# Modules.net
KiCad netlist of a schematic drawn in Altium Designer
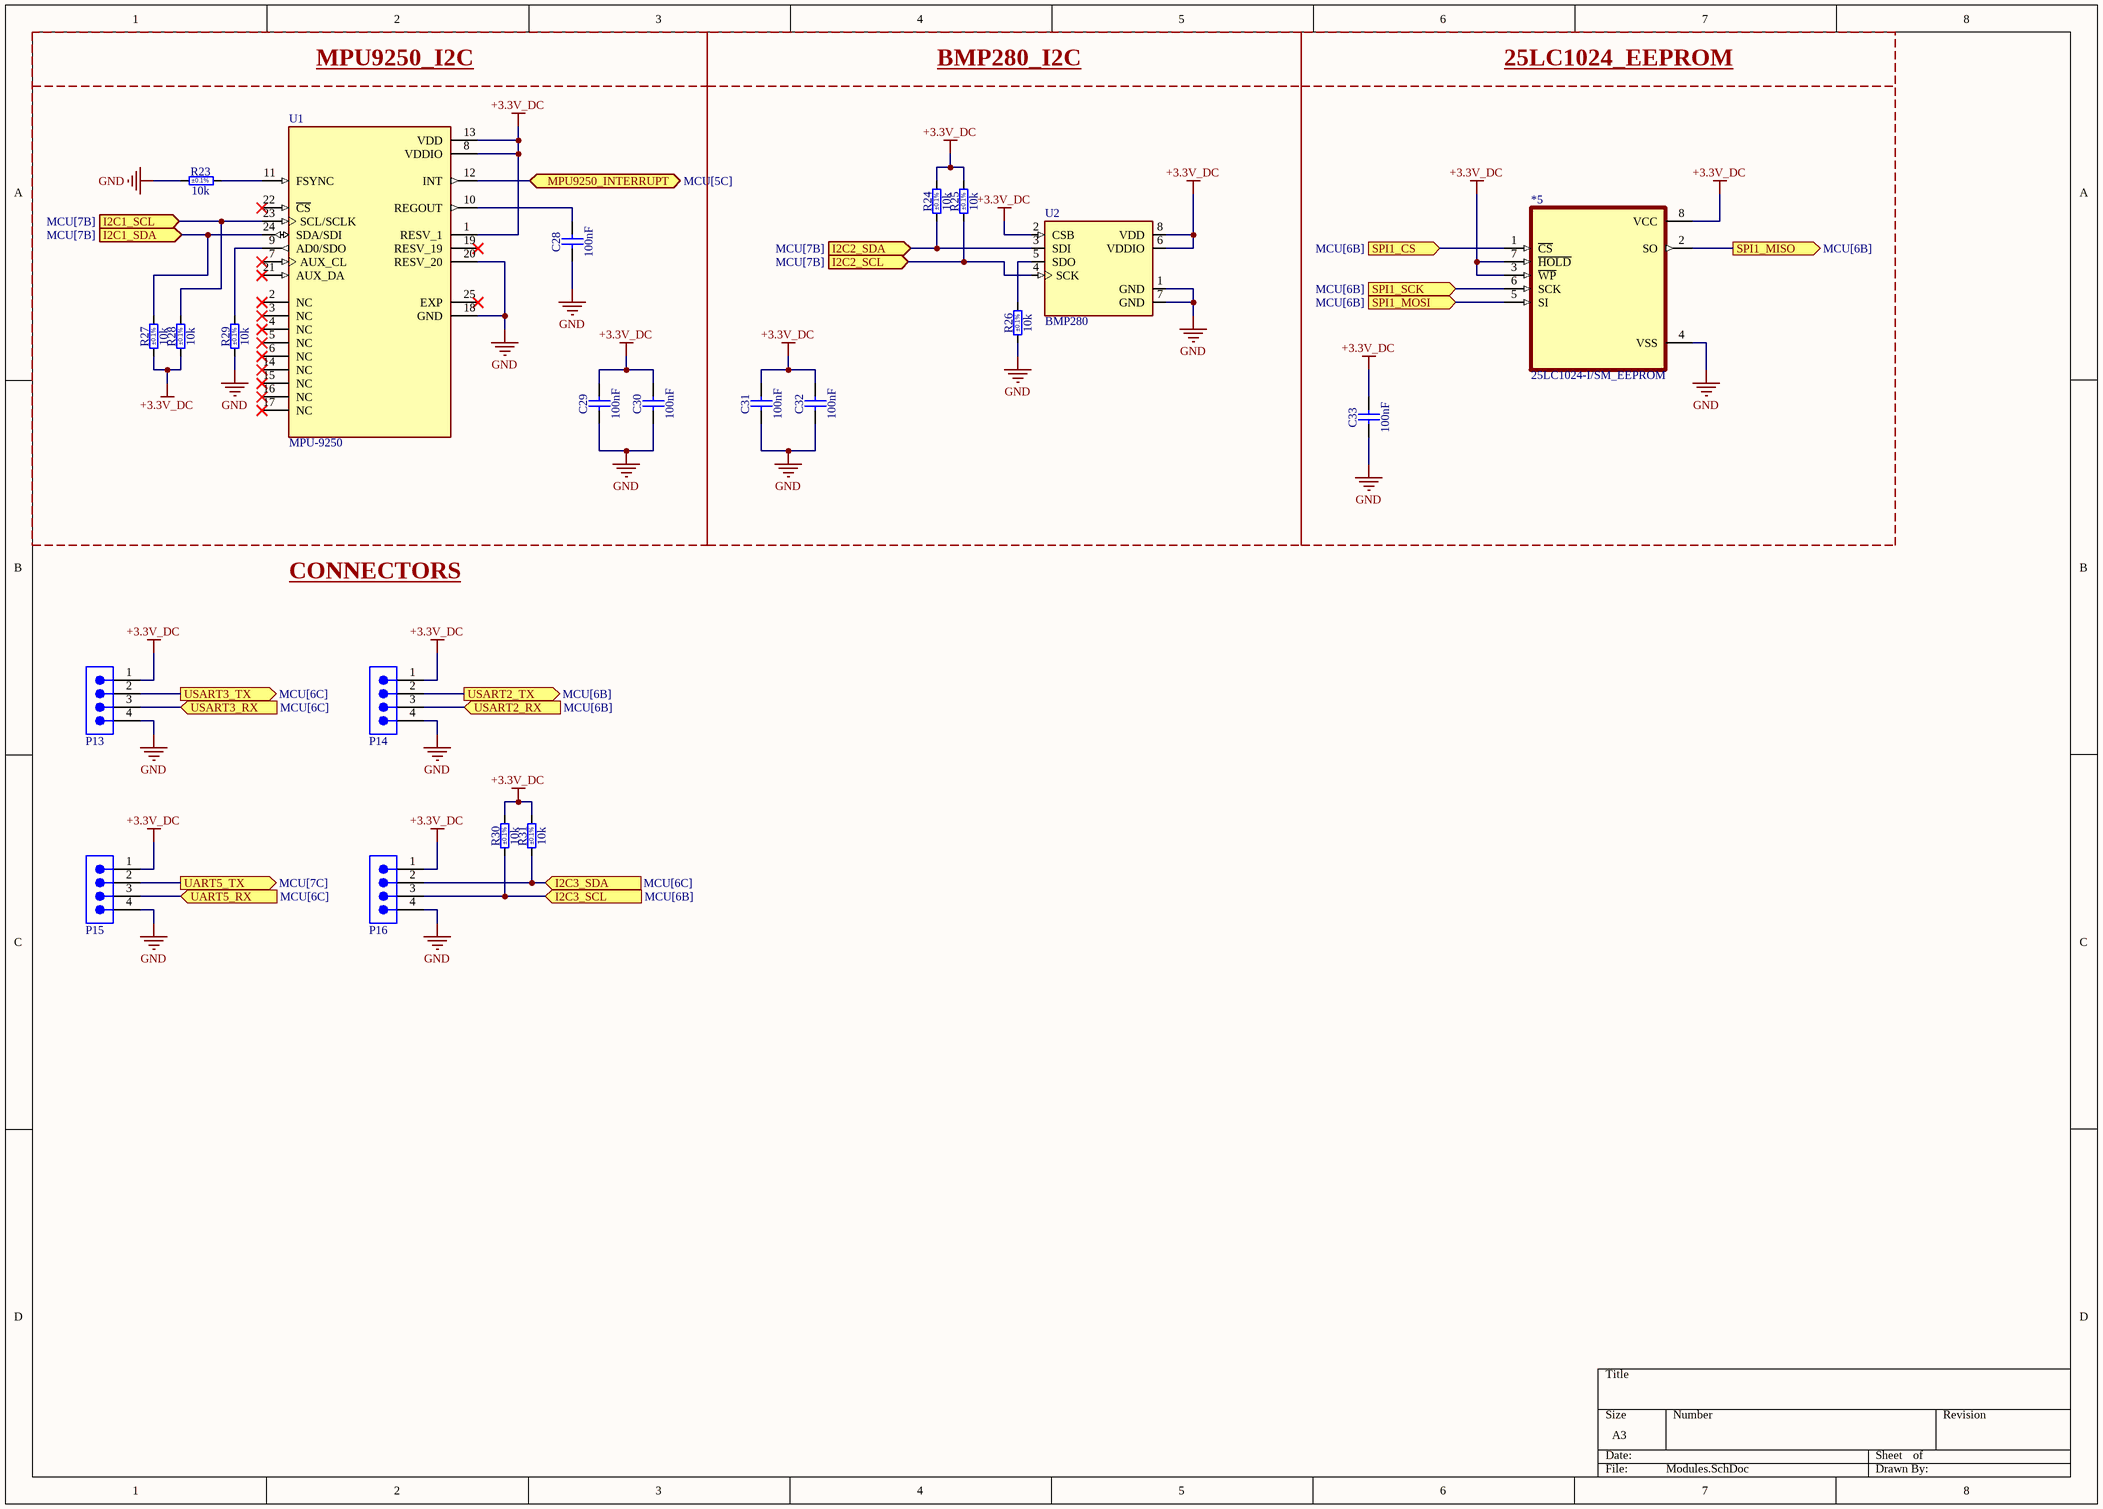
[diagram p0: Modules.SchDoc]

(export (version "E")
  (design (tool "Eeschema 10.0.6"))
  (components
    (comp (ref "*5")
      (value "25LC1024-I/SM_EEPROM")
      (footprint "25LC1024-I/SM_EEPROM")
      (libsource (lib "UDEMY_Library") (part "25LC1024-I/SM_EEPROM"))
    )
    (comp (ref "C28")
      (value "100nF")
      (footprint "CAPC2012X135N")
      (description "Non-polarised capacitor")
      (fields
        (field (name "PART NUMBER") "CC0805_100NF_50V_10%_X7R")
        (field (name "VOLTAGE") "50V")
        (field (name "AUTHOR") "CERN DEM JLC")
      )
      (libsource (lib "Capacitors") (part "Capacitor - non polarized"))
    )
    (comp (ref "C29")
      (value "100nF")
      (footprint "CAPC2012X135N")
      (description "Non-polarised capacitor")
      (fields
        (field (name "PART NUMBER") "CC0805_100NF_50V_10%_X7R")
        (field (name "VOLTAGE") "50V")
        (field (name "AUTHOR") "CERN DEM JLC")
      )
      (libsource (lib "Capacitors") (part "Capacitor - non polarized"))
    )
    (comp (ref "C30")
      (value "100nF")
      (footprint "CAPC2012X135N")
      (description "Non-polarised capacitor")
      (fields
        (field (name "PART NUMBER") "CC0805_100NF_50V_10%_X7R")
        (field (name "VOLTAGE") "50V")
        (field (name "AUTHOR") "CERN DEM JLC")
      )
      (libsource (lib "Capacitors") (part "Capacitor - non polarized"))
    )
    (comp (ref "C31")
      (value "100nF")
      (footprint "CAPC2012X135N")
      (description "Non-polarised capacitor")
      (fields
        (field (name "PART NUMBER") "CC0805_100NF_50V_10%_X7R")
        (field (name "VOLTAGE") "50V")
        (field (name "AUTHOR") "CERN DEM JLC")
      )
      (libsource (lib "Capacitors") (part "Capacitor - non polarized"))
    )
    (comp (ref "C32")
      (value "100nF")
      (footprint "CAPC2012X135N")
      (description "Non-polarised capacitor")
      (fields
        (field (name "PART NUMBER") "CC0805_100NF_50V_10%_X7R")
        (field (name "VOLTAGE") "50V")
        (field (name "AUTHOR") "CERN DEM JLC")
      )
      (libsource (lib "Capacitors") (part "Capacitor - non polarized"))
    )
    (comp (ref "C33")
      (value "100nF")
      (footprint "CAPC2012X135N")
      (description "Non-polarised capacitor")
      (fields
        (field (name "PART NUMBER") "CC0805_100NF_50V_10%_X7R")
        (field (name "VOLTAGE") "50V")
        (field (name "AUTHOR") "CERN DEM JLC")
      )
      (libsource (lib "Capacitors") (part "Capacitor - non polarized"))
    )
    (comp (ref "P13")
      (value "691322310004")
      (footprint "691322310004")
      (description "WR-TBL Series 322 Horizontal PCB Header, THT, pitch 3.81mm, 4p")
      (fields (field (name "MANUFACTURER") "Wurth Elektronik"))
      (libsource (lib "WE - Electromechanical Components") (part "TBL - 1R - 04P - Male"))
    )
    (comp (ref "P14")
      (value "691322310004")
      (footprint "691322310004")
      (description "WR-TBL Series 322 Horizontal PCB Header, THT, pitch 3.81mm, 4p")
      (fields (field (name "MANUFACTURER") "Wurth Elektronik"))
      (libsource (lib "WE - Electromechanical Components") (part "TBL - 1R - 04P - Male"))
    )
    (comp (ref "P15")
      (value "691322310004")
      (footprint "691322310004")
      (description "WR-TBL Series 322 Horizontal PCB Header, THT, pitch 3.81mm, 4p")
      (fields (field (name "MANUFACTURER") "Wurth Elektronik"))
      (libsource (lib "WE - Electromechanical Components") (part "TBL - 1R - 04P - Male"))
    )
    (comp (ref "P16")
      (value "691322310004")
      (footprint "691322310004")
      (description "WR-TBL Series 322 Horizontal PCB Header, THT, pitch 3.81mm, 4p")
      (fields (field (name "MANUFACTURER") "Wurth Elektronik"))
      (libsource (lib "WE - Electromechanical Components") (part "TBL - 1R - 04P - Male"))
    )
    (comp (ref "R23")
      (value "10k")
      (footprint "RESC2012X60N")
      (description "Resistor - 0.1%")
      (fields
        (field (name "TOLERANCE") "±0.1%")
        (field (name "PART NUMBER") "R0805_10K_0.1%_0.1W_10PPM")
        (field (name "POWER") "0.1W")
        (field (name "AUTHOR") "CERN DEM JLC")
      )
      (libsource (lib "Resistors") (part "Resistor - 0.1%"))
    )
    (comp (ref "R24")
      (value "10k")
      (footprint "RESC2012X60N")
      (description "Resistor - 0.1%")
      (fields
        (field (name "TOLERANCE") "±0.1%")
        (field (name "PART NUMBER") "R0805_10K_0.1%_0.1W_10PPM")
        (field (name "POWER") "0.1W")
        (field (name "AUTHOR") "CERN DEM JLC")
      )
      (libsource (lib "Resistors") (part "Resistor - 0.1%"))
    )
    (comp (ref "R25")
      (value "10k")
      (footprint "RESC2012X60N")
      (description "Resistor - 0.1%")
      (fields
        (field (name "TOLERANCE") "±0.1%")
        (field (name "PART NUMBER") "R0805_10K_0.1%_0.1W_10PPM")
        (field (name "POWER") "0.1W")
        (field (name "AUTHOR") "CERN DEM JLC")
      )
      (libsource (lib "Resistors") (part "Resistor - 0.1%"))
    )
    (comp (ref "R26")
      (value "10k")
      (footprint "RESC2012X60N")
      (description "Resistor - 0.1%")
      (fields
        (field (name "TOLERANCE") "±0.1%")
        (field (name "PART NUMBER") "R0805_10K_0.1%_0.1W_10PPM")
        (field (name "POWER") "0.1W")
        (field (name "AUTHOR") "CERN DEM JLC")
      )
      (libsource (lib "Resistors") (part "Resistor - 0.1%"))
    )
    (comp (ref "R27")
      (value "10k")
      (footprint "RESC2012X60N")
      (description "Resistor - 0.1%")
      (fields
        (field (name "TOLERANCE") "±0.1%")
        (field (name "PART NUMBER") "R0805_10K_0.1%_0.1W_10PPM")
        (field (name "POWER") "0.1W")
        (field (name "AUTHOR") "CERN DEM JLC")
      )
      (libsource (lib "Resistors") (part "Resistor - 0.1%"))
    )
    (comp (ref "R28")
      (value "10k")
      (footprint "RESC2012X60N")
      (description "Resistor - 0.1%")
      (fields
        (field (name "TOLERANCE") "±0.1%")
        (field (name "PART NUMBER") "R0805_10K_0.1%_0.1W_10PPM")
        (field (name "POWER") "0.1W")
        (field (name "AUTHOR") "CERN DEM JLC")
      )
      (libsource (lib "Resistors") (part "Resistor - 0.1%"))
    )
    (comp (ref "R29")
      (value "10k")
      (footprint "RESC2012X60N")
      (description "Resistor - 0.1%")
      (fields
        (field (name "TOLERANCE") "±0.1%")
        (field (name "PART NUMBER") "R0805_10K_0.1%_0.1W_10PPM")
        (field (name "POWER") "0.1W")
        (field (name "AUTHOR") "CERN DEM JLC")
      )
      (libsource (lib "Resistors") (part "Resistor - 0.1%"))
    )
    (comp (ref "R30")
      (value "10k")
      (footprint "RESC2012X60N")
      (description "Resistor - 0.1%")
      (fields
        (field (name "TOLERANCE") "±0.1%")
        (field (name "PART NUMBER") "R0805_10K_0.1%_0.1W_10PPM")
        (field (name "POWER") "0.1W")
        (field (name "AUTHOR") "CERN DEM JLC")
      )
      (libsource (lib "Resistors") (part "Resistor - 0.1%"))
    )
    (comp (ref "R31")
      (value "10k")
      (footprint "RESC2012X60N")
      (description "Resistor - 0.1%")
      (fields
        (field (name "TOLERANCE") "±0.1%")
        (field (name "PART NUMBER") "R0805_10K_0.1%_0.1W_10PPM")
        (field (name "POWER") "0.1W")
        (field (name "AUTHOR") "CERN DEM JLC")
      )
      (libsource (lib "Resistors") (part "Resistor - 0.1%"))
    )
    (comp (ref "U1")
      (value "MPU-9250")
      (footprint "QFN40P300X300X105-25N")
      (fields (field (name "MF") "TDK InvenSense"))
      (libsource (lib "MPU-9250") (part "MPU-9250"))
    )
    (comp (ref "U2")
      (value "BMP280")
      (footprint "XDCR_BMP280")
      (description "BMP280 Absolute Barometric Pressure Sensor for Battery Powered Devices 2 x 2.5mm")
      (libsource (lib "BMP280") (part "BMP280"))
    )
  )
  (nets
    (net (code "1") (name "+3.3V_DC") (class "Default")
      (node (ref "*5") (pin "3") (pinfunction "~{WP}_3") (pintype "input"))
      (node (ref "*5") (pin "7") (pinfunction "~{HOLD}_7") (pintype "input"))
      (node (ref "*5") (pin "8") (pinfunction "VCC_8") (pintype "power_in"))
      (node (ref "C29") (pin "2") (pinfunction "2_2") (pintype "passive"))
      (node (ref "C30") (pin "2") (pinfunction "2_2") (pintype "passive"))
      (node (ref "C31") (pin "2") (pinfunction "2_2") (pintype "passive"))
      (node (ref "C32") (pin "2") (pinfunction "2_2") (pintype "passive"))
      (node (ref "C33") (pin "2") (pinfunction "2_2") (pintype "passive"))
      (node (ref "P13") (pin "1") (pinfunction "1_1") (pintype "passive"))
      (node (ref "P14") (pin "1") (pinfunction "1_1") (pintype "passive"))
      (node (ref "P15") (pin "1") (pinfunction "1_1") (pintype "passive"))
      (node (ref "P16") (pin "1") (pinfunction "1_1") (pintype "passive"))
      (node (ref "R24") (pin "2") (pinfunction "2_2") (pintype "passive"))
      (node (ref "R25") (pin "2") (pinfunction "2_2") (pintype "passive"))
      (node (ref "R27") (pin "1") (pinfunction "1_1") (pintype "passive"))
      (node (ref "R28") (pin "1") (pinfunction "1_1") (pintype "passive"))
      (node (ref "R30") (pin "2") (pinfunction "2_2") (pintype "passive"))
      (node (ref "R31") (pin "2") (pinfunction "2_2") (pintype "passive"))
      (node (ref "U1") (pin "1") (pinfunction "RESV_1_1") (pintype "power_in"))
      (node (ref "U1") (pin "13") (pinfunction "VDD_13") (pintype "power_in"))
      (node (ref "U1") (pin "8") (pinfunction "VDDIO_8") (pintype "power_in"))
      (node (ref "U2") (pin "2") (pinfunction "CSB_2") (pintype "input"))
      (node (ref "U2") (pin "6") (pinfunction "VDDIO_6") (pintype "power_in"))
      (node (ref "U2") (pin "8") (pinfunction "VDD_8") (pintype "power_in"))
    )
    (net (code "2") (name "/I2C1_SCL") (class "Default")
      (node (ref "R28") (pin "2") (pinfunction "2_2") (pintype "passive"))
      (node (ref "U1") (pin "23") (pinfunction "SCL/SCLK_23") (pintype "input"))
    )
    (net (code "3") (name "/I2C1_SDA") (class "Default")
      (node (ref "R27") (pin "2") (pinfunction "2_2") (pintype "passive"))
      (node (ref "U1") (pin "24") (pinfunction "SDA/SDI_24") (pintype "bidirectional"))
    )
    (net (code "4") (name "/I2C2_SCL") (class "Default")
      (node (ref "R25") (pin "1") (pinfunction "1_1") (pintype "passive"))
      (node (ref "U2") (pin "4") (pinfunction "SCK_4") (pintype "input"))
    )
    (net (code "5") (name "/I2C2_SDA") (class "Default")
      (node (ref "R24") (pin "1") (pinfunction "1_1") (pintype "passive"))
      (node (ref "U2") (pin "3") (pinfunction "SDI_3") (pintype "bidirectional"))
    )
    (net (code "6") (name "/I2C3_SCL") (class "Default")
      (node (ref "P16") (pin "3") (pinfunction "3_3") (pintype "passive"))
      (node (ref "R30") (pin "1") (pinfunction "1_1") (pintype "passive"))
    )
    (net (code "7") (name "/I2C3_SDA") (class "Default")
      (node (ref "P16") (pin "2") (pinfunction "2_2") (pintype "passive"))
      (node (ref "R31") (pin "1") (pinfunction "1_1") (pintype "passive"))
    )
    (net (code "8") (name "/MPU9250_INTERRUPT") (class "Default")
      (node (ref "U1") (pin "12") (pinfunction "INT_12") (pintype "output"))
    )
    (net (code "9") (name "/SPI1_CS") (class "Default")
      (node (ref "*5") (pin "1") (pinfunction "~{CS}_1") (pintype "input"))
    )
    (net (code "10") (name "/SPI1_MISO") (class "Default")
      (node (ref "*5") (pin "2") (pinfunction "SO_2") (pintype "output"))
    )
    (net (code "11") (name "/SPI1_MOSI") (class "Default")
      (node (ref "*5") (pin "5") (pinfunction "SI_5") (pintype "input"))
    )
    (net (code "12") (name "/SPI1_SCK") (class "Default")
      (node (ref "*5") (pin "6") (pinfunction "SCK_6") (pintype "input"))
    )
    (net (code "13") (name "/UART5_RX") (class "Default")
      (node (ref "P15") (pin "3") (pinfunction "3_3") (pintype "passive"))
    )
    (net (code "14") (name "/UART5_TX") (class "Default")
      (node (ref "P15") (pin "2") (pinfunction "2_2") (pintype "passive"))
    )
    (net (code "15") (name "/USART2_RX") (class "Default")
      (node (ref "P14") (pin "3") (pinfunction "3_3") (pintype "passive"))
    )
    (net (code "16") (name "/USART2_TX") (class "Default")
      (node (ref "P14") (pin "2") (pinfunction "2_2") (pintype "passive"))
    )
    (net (code "17") (name "/USART3_RX") (class "Default")
      (node (ref "P13") (pin "3") (pinfunction "3_3") (pintype "passive"))
    )
    (net (code "18") (name "/USART3_TX") (class "Default")
      (node (ref "P13") (pin "2") (pinfunction "2_2") (pintype "passive"))
    )
    (net (code "19") (name "GND") (class "Default")
      (node (ref "*5") (pin "4") (pinfunction "VSS_4") (pintype "power_in"))
      (node (ref "C28") (pin "1") (pinfunction "1_1") (pintype "passive"))
      (node (ref "C29") (pin "1") (pinfunction "1_1") (pintype "passive"))
      (node (ref "C30") (pin "1") (pinfunction "1_1") (pintype "passive"))
      (node (ref "C31") (pin "1") (pinfunction "1_1") (pintype "passive"))
      (node (ref "C32") (pin "1") (pinfunction "1_1") (pintype "passive"))
      (node (ref "C33") (pin "1") (pinfunction "1_1") (pintype "passive"))
      (node (ref "P13") (pin "4") (pinfunction "4_4") (pintype "passive"))
      (node (ref "P14") (pin "4") (pinfunction "4_4") (pintype "passive"))
      (node (ref "P15") (pin "4") (pinfunction "4_4") (pintype "passive"))
      (node (ref "P16") (pin "4") (pinfunction "4_4") (pintype "passive"))
      (node (ref "R23") (pin "1") (pinfunction "1_1") (pintype "passive"))
      (node (ref "R26") (pin "1") (pinfunction "1_1") (pintype "passive"))
      (node (ref "R29") (pin "1") (pinfunction "1_1") (pintype "passive"))
      (node (ref "U1") (pin "18") (pinfunction "GND_18") (pintype "power_in"))
      (node (ref "U1") (pin "20") (pinfunction "RESV_20_20") (pintype "power_in"))
      (node (ref "U2") (pin "1") (pinfunction "GND_1") (pintype "power_in"))
      (node (ref "U2") (pin "7") (pinfunction "GND_7") (pintype "power_in"))
    )
    (net (code "20") (name "Net-(U1-AD0{slash}SDO)") (class "Default")
      (node (ref "R29") (pin "2") (pinfunction "2_2") (pintype "passive"))
      (node (ref "U1") (pin "9") (pinfunction "AD0/SDO_9") (pintype "output"))
    )
    (net (code "21") (name "Net-(U1-FSYNC)") (class "Default")
      (node (ref "R23") (pin "2") (pinfunction "2_2") (pintype "passive"))
      (node (ref "U1") (pin "11") (pinfunction "FSYNC_11") (pintype "input"))
    )
    (net (code "22") (name "Net-(U1-REGOUT)") (class "Default")
      (node (ref "C28") (pin "2") (pinfunction "2_2") (pintype "passive"))
      (node (ref "U1") (pin "10") (pinfunction "REGOUT_10") (pintype "output"))
    )
    (net (code "23") (name "Net-(U2-SDO)") (class "Default")
      (node (ref "R26") (pin "2") (pinfunction "2_2") (pintype "passive"))
      (node (ref "U2") (pin "5") (pinfunction "SDO_5") (pintype "bidirectional"))
    )
    (net (code "24") (name "unconnected-(U1-AUX_CL-Pad7)") (class "Default")
      (node (ref "U1") (pin "7") (pinfunction "AUX_CL_7") (pintype "input+no_connect"))
    )
    (net (code "25") (name "unconnected-(U1-AUX_DA-Pad21)") (class "Default")
      (node (ref "U1") (pin "21") (pinfunction "AUX_DA_21") (pintype "input+no_connect"))
    )
    (net (code "26") (name "unconnected-(U1-EXP-Pad25)") (class "Default")
      (node (ref "U1") (pin "25") (pinfunction "EXP_25") (pintype "passive+no_connect"))
    )
    (net (code "27") (name "unconnected-(U1-NC-Pad2)") (class "Default")
      (node (ref "U1") (pin "2") (pinfunction "NC_2") (pintype "passive+no_connect"))
    )
    (net (code "28") (name "unconnected-(U1-NC-Pad3)") (class "Default")
      (node (ref "U1") (pin "3") (pinfunction "NC_3") (pintype "passive+no_connect"))
    )
    (net (code "29") (name "unconnected-(U1-NC-Pad4)") (class "Default")
      (node (ref "U1") (pin "4") (pinfunction "NC_4") (pintype "passive+no_connect"))
    )
    (net (code "30") (name "unconnected-(U1-NC-Pad5)") (class "Default")
      (node (ref "U1") (pin "5") (pinfunction "NC_5") (pintype "passive+no_connect"))
    )
    (net (code "31") (name "unconnected-(U1-NC-Pad6)") (class "Default")
      (node (ref "U1") (pin "6") (pinfunction "NC_6") (pintype "passive+no_connect"))
    )
    (net (code "32") (name "unconnected-(U1-NC-Pad14)") (class "Default")
      (node (ref "U1") (pin "14") (pinfunction "NC_14") (pintype "passive+no_connect"))
    )
    (net (code "33") (name "unconnected-(U1-NC-Pad15)") (class "Default")
      (node (ref "U1") (pin "15") (pinfunction "NC_15") (pintype "passive+no_connect"))
    )
    (net (code "34") (name "unconnected-(U1-NC-Pad16)") (class "Default")
      (node (ref "U1") (pin "16") (pinfunction "NC_16") (pintype "passive+no_connect"))
    )
    (net (code "35") (name "unconnected-(U1-NC-Pad17)") (class "Default")
      (node (ref "U1") (pin "17") (pinfunction "NC_17") (pintype "passive+no_connect"))
    )
    (net (code "36") (name "unconnected-(U1-RESV_19-Pad19)") (class "Default")
      (node (ref "U1") (pin "19") (pinfunction "RESV_19_19") (pintype "passive+no_connect"))
    )
    (net (code "37") (name "unconnected-(U1-~{CS}-Pad22)") (class "Default")
      (node (ref "U1") (pin "22") (pinfunction "~{CS}_22") (pintype "input+no_connect"))
    )
  )
)
